# Optic_sensor_quad.net
KiCad netlist of a schematic drawn in Altium Designer
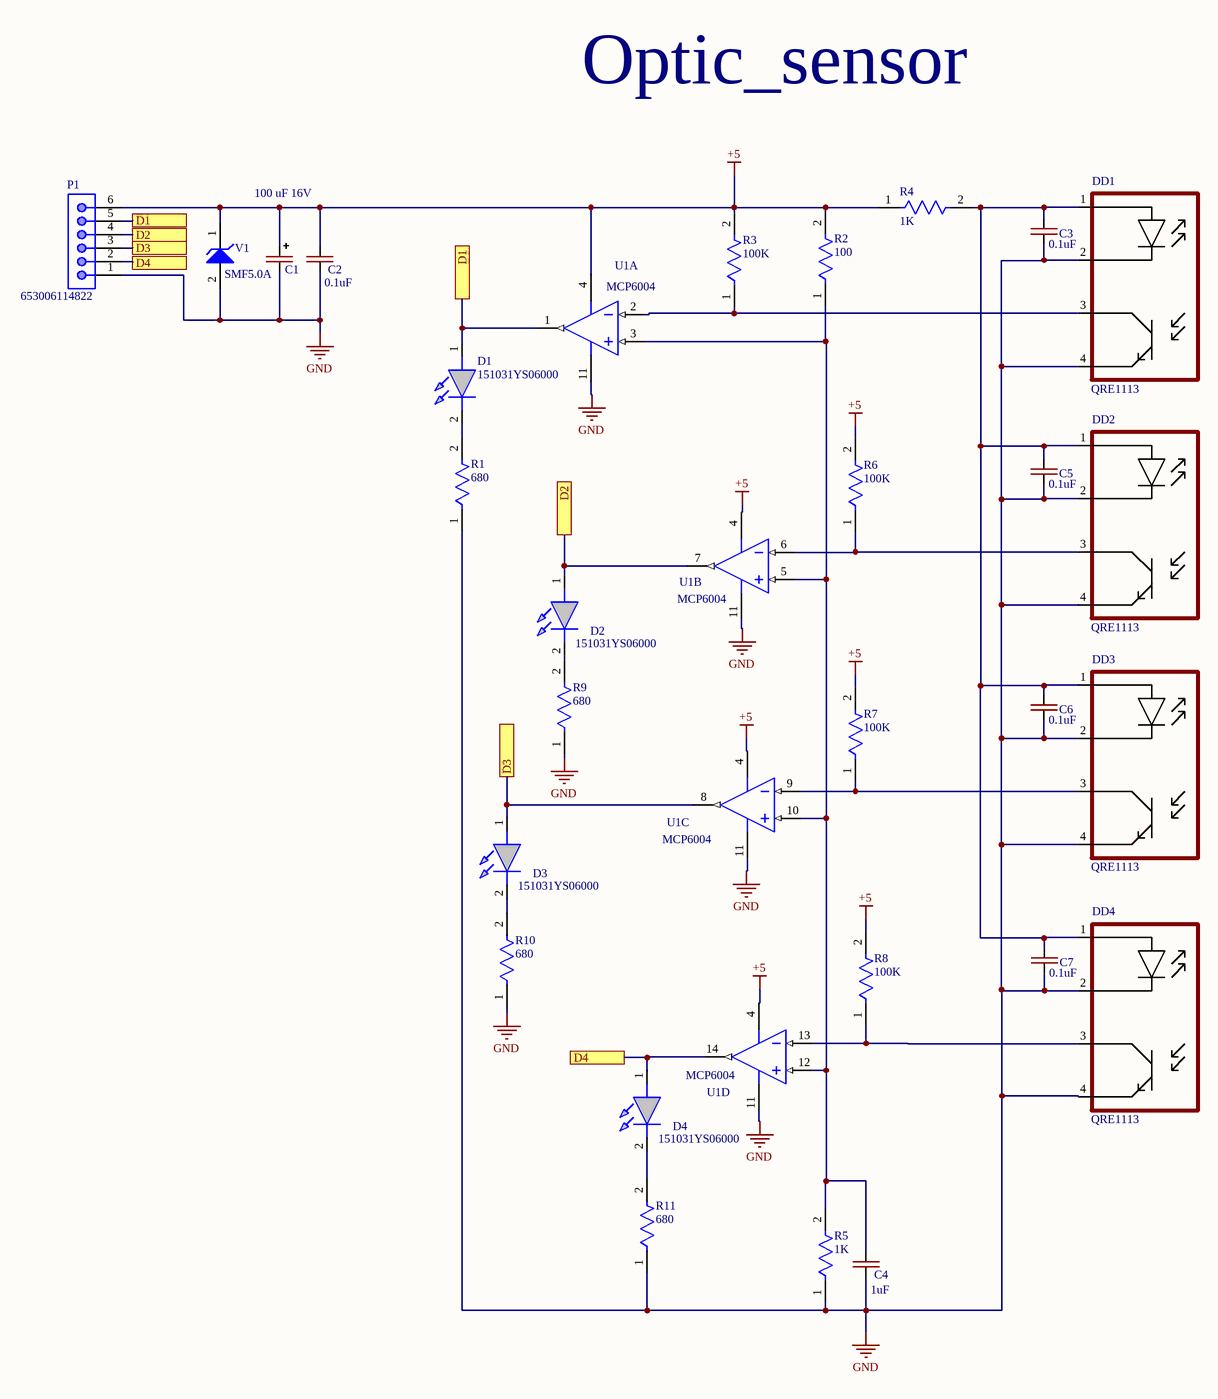
[diagram p0: Optic_sensor_quad.SchDoc]

(export (version "E")
  (design (tool "Eeschema 10.0.6"))
  (components
    (comp (ref "C1")
      (value "100 uF 16V")
      (footprint "CAP-TAN-C")
      (description "25 uF 16V")
      (libsource (lib "PASSIVE_COMPONENTS") (part "CAP-POLAR"))
    )
    (comp (ref "C2")
      (value "0.1uF")
      (footprint "CAP-0603")
      (libsource (lib "PASSIVE_COMPONENTS") (part "CAP-NON-POLAR"))
    )
    (comp (ref "C3")
      (value "0.1uF")
      (footprint "CAP-0603")
      (libsource (lib "PASSIVE_COMPONENTS") (part "CAP-NON-POLAR"))
    )
    (comp (ref "C4")
      (value "1uF")
      (footprint "CAP-0603")
      (libsource (lib "PASSIVE_COMPONENTS") (part "CAP-NON-POLAR"))
    )
    (comp (ref "C5")
      (value "0.1uF")
      (footprint "CAP-0603")
      (libsource (lib "PASSIVE_COMPONENTS") (part "CAP-NON-POLAR"))
    )
    (comp (ref "C6")
      (value "0.1uF")
      (footprint "CAP-0603")
      (libsource (lib "PASSIVE_COMPONENTS") (part "CAP-NON-POLAR"))
    )
    (comp (ref "C7")
      (value "0.1uF")
      (footprint "CAP-0603")
      (libsource (lib "PASSIVE_COMPONENTS") (part "CAP-NON-POLAR"))
    )
    (comp (ref "D1")
      (value "151031YS06000")
      (footprint "LED_GREEN")
      (description "WURTH ELEKTRONIK - 151031YS06000 - LED, Yellow, Through Hole, T-1 (3mm), 30 mA, 2 V, 590 nm")
      (fields (field (name "MOUSER PART NUMBER") "710-151031YS06000"))
      (libsource (lib "Optic-LED") (part "LED"))
    )
    (comp (ref "D2")
      (value "151031YS06000")
      (footprint "LED_GREEN")
      (description "WURTH ELEKTRONIK - 151031YS06000 - LED, Yellow, Through Hole, T-1 (3mm), 30 mA, 2 V, 590 nm")
      (fields (field (name "MOUSER PART NUMBER") "710-151031YS06000"))
      (libsource (lib "Optic-LED") (part "LED"))
    )
    (comp (ref "D3")
      (value "151031YS06000")
      (footprint "LED_GREEN")
      (description "WURTH ELEKTRONIK - 151031YS06000 - LED, Yellow, Through Hole, T-1 (3mm), 30 mA, 2 V, 590 nm")
      (fields (field (name "MOUSER PART NUMBER") "710-151031YS06000"))
      (libsource (lib "Optic-LED") (part "LED"))
    )
    (comp (ref "D4")
      (value "151031YS06000")
      (footprint "LED_GREEN")
      (description "WURTH ELEKTRONIK - 151031YS06000 - LED, Yellow, Through Hole, T-1 (3mm), 30 mA, 2 V, 590 nm")
      (fields (field (name "MOUSER PART NUMBER") "710-151031YS06000"))
      (libsource (lib "Optic-LED") (part "LED"))
    )
    (comp (ref "DD1") (value "QRE1113") (footprint "QRE1113") (libsource (lib "QRE1113") (part "QRE1113")))
    (comp (ref "DD2") (value "QRE1113") (footprint "QRE1113") (libsource (lib "QRE1113") (part "QRE1113")))
    (comp (ref "DD3") (value "QRE1113") (footprint "QRE1113") (libsource (lib "QRE1113") (part "QRE1113")))
    (comp (ref "DD4") (value "QRE1113") (footprint "QRE1113") (libsource (lib "QRE1113") (part "QRE1113")))
    (comp (ref "P1")
      (value "653006114822")
      (footprint "653006114822")
      (description "WR-WTB THT Male Vertical Shrouded Header, pitch 1.25mm, 6p")
      (fields (field (name "PUBLISHER") "Wurth Elektronik"))
      (libsource (lib "Altium_WR-WTB (rev20a)") (part "653006114822"))
    )
    (comp (ref "R1")
      (value "680")
      (footprint "RES-0603")
      (libsource (lib "PASSIVE_COMPONENTS") (part "RES-CONST"))
    )
    (comp (ref "R2")
      (value "100")
      (footprint "RES-0603")
      (libsource (lib "PASSIVE_COMPONENTS") (part "RES-CONST"))
    )
    (comp (ref "R3")
      (value "100K")
      (footprint "RES-0603")
      (libsource (lib "PASSIVE_COMPONENTS") (part "RES-CONST"))
    )
    (comp (ref "R4")
      (value "1K")
      (footprint "RES-0603")
      (libsource (lib "PASSIVE_COMPONENTS") (part "RES-CONST"))
    )
    (comp (ref "R5")
      (value "1K")
      (footprint "RES-0603")
      (libsource (lib "PASSIVE_COMPONENTS") (part "RES-CONST"))
    )
    (comp (ref "R6")
      (value "100K")
      (footprint "RES-0603")
      (libsource (lib "PASSIVE_COMPONENTS") (part "RES-CONST"))
    )
    (comp (ref "R7")
      (value "100K")
      (footprint "RES-0603")
      (libsource (lib "PASSIVE_COMPONENTS") (part "RES-CONST"))
    )
    (comp (ref "R8")
      (value "100K")
      (footprint "RES-0603")
      (libsource (lib "PASSIVE_COMPONENTS") (part "RES-CONST"))
    )
    (comp (ref "R9")
      (value "680")
      (footprint "RES-0603")
      (libsource (lib "PASSIVE_COMPONENTS") (part "RES-CONST"))
    )
    (comp (ref "R10")
      (value "680")
      (footprint "RES-0603")
      (libsource (lib "PASSIVE_COMPONENTS") (part "RES-CONST"))
    )
    (comp (ref "R11")
      (value "680")
      (footprint "RES-0603")
      (libsource (lib "PASSIVE_COMPONENTS") (part "RES-CONST"))
    )
    (comp (ref "U1")
      (value "MCP6004")
      (footprint "TSSOP-ST14_L")
      (description "MCP6004 TSSOP")
      (libsource (lib "Integrated_Circuts") (part "MCP6004"))
    )
    (comp (ref "V1")
      (value "SMF5.0A")
      (footprint "SOD-123")
      (description "SMF5.0A SOD-123")
      (libsource (lib "Diodes") (part "SMF5.0A"))
    )
  )
  (nets
    (net (code "1") (name "+5") (class "Default")
      (node (ref "C1") (pin "1") (pinfunction "+_1") (pintype "passive"))
      (node (ref "C2") (pin "2") (pinfunction "2_2") (pintype "passive"))
      (node (ref "P1") (pin "6") (pinfunction "6_6") (pintype "passive"))
      (node (ref "R2") (pin "2") (pinfunction "2_2") (pintype "passive"))
      (node (ref "R3") (pin "2") (pinfunction "2_2") (pintype "passive"))
      (node (ref "R4") (pin "1") (pinfunction "1_1") (pintype "passive"))
      (node (ref "R6") (pin "2") (pinfunction "2_2") (pintype "passive"))
      (node (ref "R7") (pin "2") (pinfunction "2_2") (pintype "passive"))
      (node (ref "R8") (pin "2") (pinfunction "2_2") (pintype "passive"))
      (node (ref "U1") (pin "4") (pinfunction "VDD_4") (pintype "power_in"))
      (node (ref "V1") (pin "1") (pinfunction "K_1") (pintype "passive"))
    )
    (net (code "2") (name "/D1") (class "Default")
      (node (ref "D1") (pin "1") (pinfunction "A_1") (pintype "passive"))
      (node (ref "P1") (pin "5") (pinfunction "5_5") (pintype "passive"))
      (node (ref "U1") (pin "1") (pinfunction "VOUTA_1") (pintype "output"))
    )
    (net (code "3") (name "/D2") (class "Default")
      (node (ref "D2") (pin "1") (pinfunction "A_1") (pintype "passive"))
      (node (ref "P1") (pin "4") (pinfunction "4_4") (pintype "passive"))
      (node (ref "U1") (pin "7") (pinfunction "VOUTB_7") (pintype "output"))
    )
    (net (code "4") (name "/D3") (class "Default")
      (node (ref "D3") (pin "1") (pinfunction "A_1") (pintype "passive"))
      (node (ref "P1") (pin "3") (pinfunction "3_3") (pintype "passive"))
      (node (ref "U1") (pin "8") (pinfunction "VOUTC_8") (pintype "output"))
    )
    (net (code "5") (name "/D4") (class "Default")
      (node (ref "D4") (pin "1") (pinfunction "A_1") (pintype "passive"))
      (node (ref "P1") (pin "2") (pinfunction "2_2") (pintype "passive"))
      (node (ref "U1") (pin "14") (pinfunction "VOUTD_14") (pintype "output"))
    )
    (net (code "6") (name "GND") (class "Default")
      (node (ref "C1") (pin "2") (pinfunction "-_2") (pintype "passive"))
      (node (ref "C2") (pin "1") (pinfunction "1_1") (pintype "passive"))
      (node (ref "C3") (pin "1") (pinfunction "1_1") (pintype "passive"))
      (node (ref "C4") (pin "1") (pinfunction "1_1") (pintype "passive"))
      (node (ref "C5") (pin "1") (pinfunction "1_1") (pintype "passive"))
      (node (ref "C6") (pin "1") (pinfunction "1_1") (pintype "passive"))
      (node (ref "C7") (pin "1") (pinfunction "1_1") (pintype "passive"))
      (node (ref "DD1") (pin "2") (pinfunction "CATHODE_2") (pintype "passive"))
      (node (ref "DD1") (pin "4") (pintype "passive"))
      (node (ref "DD2") (pin "2") (pinfunction "CATHODE_2") (pintype "passive"))
      (node (ref "DD2") (pin "4") (pintype "passive"))
      (node (ref "DD3") (pin "2") (pinfunction "CATHODE_2") (pintype "passive"))
      (node (ref "DD3") (pin "4") (pintype "passive"))
      (node (ref "DD4") (pin "2") (pinfunction "CATHODE_2") (pintype "passive"))
      (node (ref "DD4") (pin "4") (pintype "passive"))
      (node (ref "P1") (pin "1") (pinfunction "1_1") (pintype "passive"))
      (node (ref "R1") (pin "1") (pinfunction "1_1") (pintype "passive"))
      (node (ref "R10") (pin "1") (pinfunction "1_1") (pintype "passive"))
      (node (ref "R11") (pin "1") (pinfunction "1_1") (pintype "passive"))
      (node (ref "R5") (pin "1") (pinfunction "1_1") (pintype "passive"))
      (node (ref "R9") (pin "1") (pinfunction "1_1") (pintype "passive"))
      (node (ref "U1") (pin "11") (pinfunction "VSS_11") (pintype "power_in"))
      (node (ref "V1") (pin "2") (pinfunction "A_2") (pintype "passive"))
    )
    (net (code "7") (name "Net-(D1-K)") (class "Default")
      (node (ref "D1") (pin "2") (pinfunction "K_2") (pintype "passive"))
      (node (ref "R1") (pin "2") (pinfunction "2_2") (pintype "passive"))
    )
    (net (code "8") (name "Net-(D2-K)") (class "Default")
      (node (ref "D2") (pin "2") (pinfunction "K_2") (pintype "passive"))
      (node (ref "R9") (pin "2") (pinfunction "2_2") (pintype "passive"))
    )
    (net (code "9") (name "Net-(D3-K)") (class "Default")
      (node (ref "D3") (pin "2") (pinfunction "K_2") (pintype "passive"))
      (node (ref "R10") (pin "2") (pinfunction "2_2") (pintype "passive"))
    )
    (net (code "10") (name "Net-(D4-K)") (class "Default")
      (node (ref "D4") (pin "2") (pinfunction "K_2") (pintype "passive"))
      (node (ref "R11") (pin "2") (pinfunction "2_2") (pintype "passive"))
    )
    (net (code "11") (name "Net-(DD1-ANODE)") (class "Default")
      (node (ref "C3") (pin "2") (pinfunction "2_2") (pintype "passive"))
      (node (ref "C5") (pin "2") (pinfunction "2_2") (pintype "passive"))
      (node (ref "C6") (pin "2") (pinfunction "2_2") (pintype "passive"))
      (node (ref "C7") (pin "2") (pinfunction "2_2") (pintype "passive"))
      (node (ref "DD1") (pin "1") (pinfunction "ANODE_1") (pintype "passive"))
      (node (ref "DD2") (pin "1") (pinfunction "ANODE_1") (pintype "passive"))
      (node (ref "DD3") (pin "1") (pinfunction "ANODE_1") (pintype "passive"))
      (node (ref "DD4") (pin "1") (pinfunction "ANODE_1") (pintype "passive"))
      (node (ref "R4") (pin "2") (pinfunction "2_2") (pintype "passive"))
    )
    (net (code "12") (name "Net-(U1A-VINA+)") (class "Default")
      (node (ref "C4") (pin "2") (pinfunction "2_2") (pintype "passive"))
      (node (ref "R2") (pin "1") (pinfunction "1_1") (pintype "passive"))
      (node (ref "R5") (pin "2") (pinfunction "2_2") (pintype "passive"))
      (node (ref "U1") (pin "10") (pinfunction "VINC+_10") (pintype "input"))
      (node (ref "U1") (pin "12") (pinfunction "VIND+_12") (pintype "input"))
      (node (ref "U1") (pin "3") (pinfunction "VINA+_3") (pintype "input"))
      (node (ref "U1") (pin "5") (pinfunction "VINB+_5") (pintype "input"))
    )
    (net (code "13") (name "Net-(U1A-VINA-)") (class "Default")
      (node (ref "DD1") (pin "3") (pintype "passive"))
      (node (ref "R3") (pin "1") (pinfunction "1_1") (pintype "passive"))
      (node (ref "U1") (pin "2") (pinfunction "VINA-_2") (pintype "input"))
    )
    (net (code "14") (name "Net-(U1B-VINB-)") (class "Default")
      (node (ref "DD2") (pin "3") (pintype "passive"))
      (node (ref "R6") (pin "1") (pinfunction "1_1") (pintype "passive"))
      (node (ref "U1") (pin "6") (pinfunction "VINB-_6") (pintype "input"))
    )
    (net (code "15") (name "Net-(U1C-VINC-)") (class "Default")
      (node (ref "DD3") (pin "3") (pintype "passive"))
      (node (ref "R7") (pin "1") (pinfunction "1_1") (pintype "passive"))
      (node (ref "U1") (pin "9") (pinfunction "VINC-_9") (pintype "input"))
    )
    (net (code "16") (name "Net-(U1D-VIND-)") (class "Default")
      (node (ref "DD4") (pin "3") (pintype "passive"))
      (node (ref "R8") (pin "1") (pinfunction "1_1") (pintype "passive"))
      (node (ref "U1") (pin "13") (pinfunction "VIND-_13") (pintype "input"))
    )
  )
)
